# CubSat2.net
KiCad netlist of a schematic drawn in Altium Designer
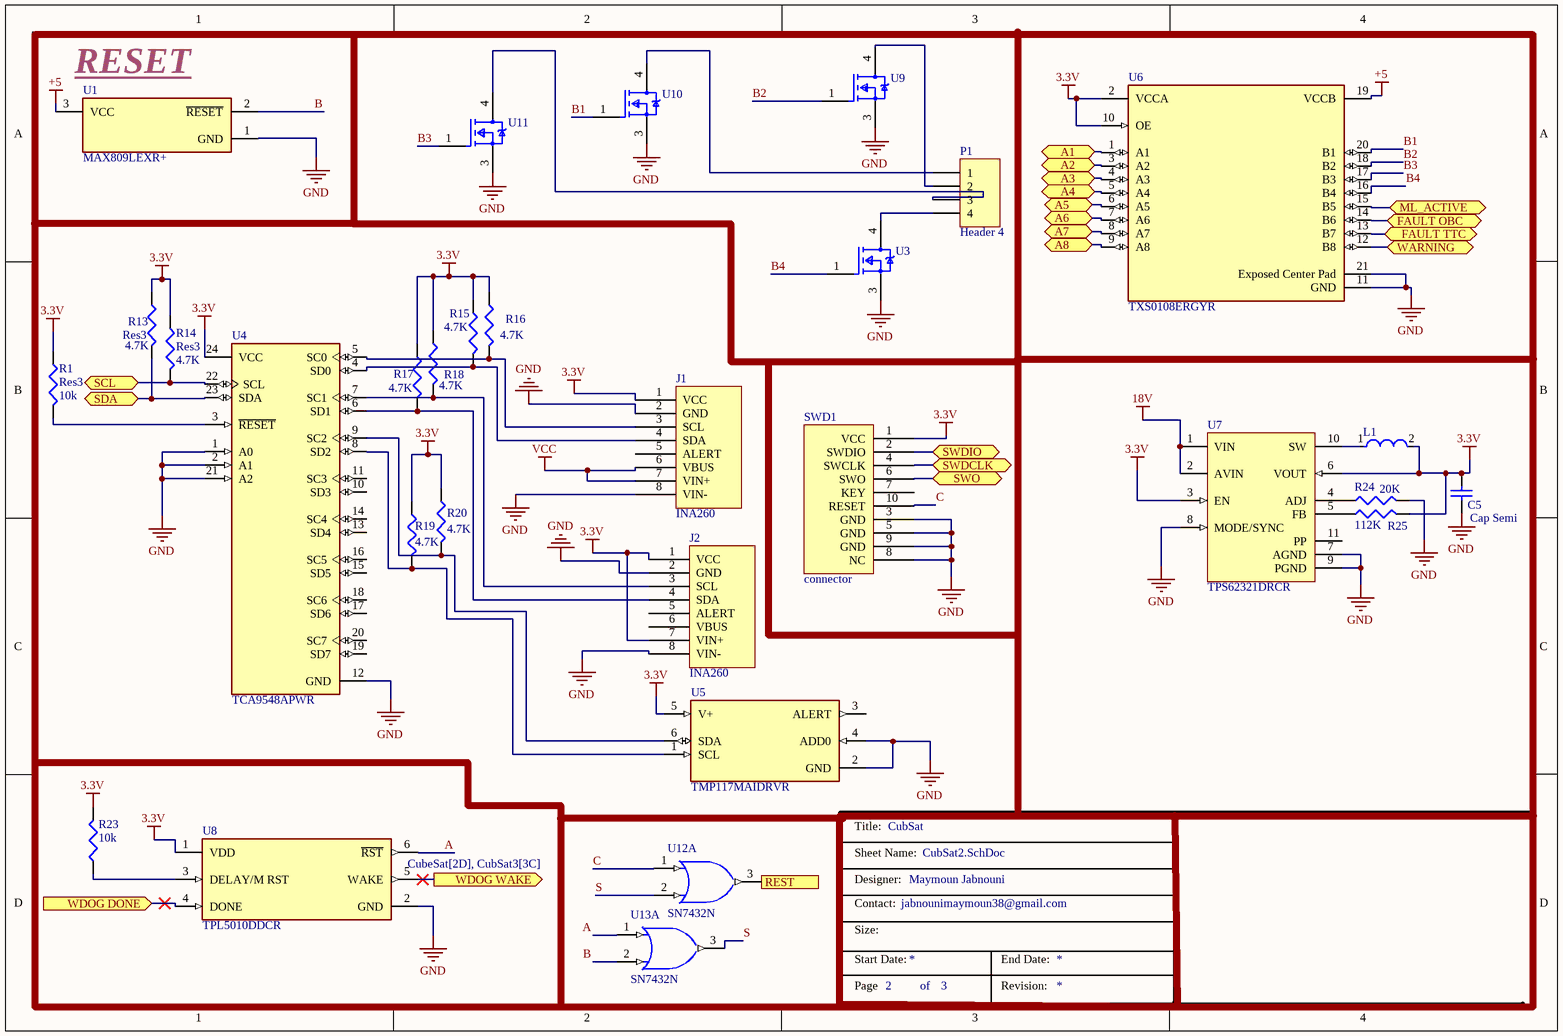
[diagram p0: CubSat2.SchDoc]

(export (version "E")
  (design (tool "Eeschema 10.0.6"))
  (components
    (comp (ref "C5")
      (value "Cap Semi")
      (footprint "C1206")
      (description "Capacitor (Semiconductor SIM Model)")
      (fields (field (name "PUBLISHER") "Altium Limited"))
      (libsource (lib "Miscellaneous Devices") (part "Cap Semi"))
    )
    (comp (ref "J1") (value "INA260") (footprint "INA260") (libsource (lib "CubSat") (part "INA260")))
    (comp (ref "J2") (value "INA260") (footprint "INA260") (libsource (lib "CubSat") (part "INA260")))
    (comp (ref "L1")
      (value "LQW31HN64NJ03L")
      (footprint "FP-LQW31HN_03-MFG")
      (description "Wire Wound RF Inductor 64nH ±5% 0.252Ω 290mA 1206")
      (fields (field (name "TOLERANCE") "5%"))
      (libsource (lib "Altium Content Vault") (part "725321dda6339637d4d059423bc1c3c"))
    )
    (comp (ref "P1")
      (value "Header 4")
      (footprint "HDR1X4")
      (description "Header, 4-Pin")
      (fields (field (name "PUBLISHER") "Altium Limited"))
      (libsource (lib "Miscellaneous Connectors") (part "Header 4"))
    )
    (comp (ref "R1")
      (value "Res3")
      (footprint "J1-0603")
      (description "Resistor")
      (fields (field (name "ALTIUM_VALUE") "10k") (field (name "PUBLISHER") "Altium Limited"))
      (libsource (lib "Miscellaneous Devices") (part "Res3"))
    )
    (comp (ref "R13")
      (value "Res3")
      (footprint "J1-0603")
      (description "Resistor")
      (fields (field (name "ALTIUM_VALUE") "4.7K") (field (name "PUBLISHER") "Altium Limited"))
      (libsource (lib "Miscellaneous Devices") (part "Res3"))
    )
    (comp (ref "R14")
      (value "Res3")
      (footprint "J1-0603")
      (description "Resistor")
      (fields (field (name "ALTIUM_VALUE") "4.7K") (field (name "PUBLISHER") "Altium Limited"))
      (libsource (lib "Miscellaneous Devices") (part "Res3"))
    )
    (comp (ref "R15")
      (value "4.7K")
      (footprint "J1-0603")
      (description "Resistor")
      (fields (field (name "Comment") "Res3") (field (name "PUBLISHER") "Altium Limited"))
      (libsource (lib "Miscellaneous Devices") (part "Res3"))
    )
    (comp (ref "R16")
      (value "4.7K")
      (footprint "J1-0603")
      (description "Resistor")
      (fields (field (name "Comment") "Res3") (field (name "PUBLISHER") "Altium Limited"))
      (libsource (lib "Miscellaneous Devices") (part "Res3"))
    )
    (comp (ref "R17")
      (value "4.7K")
      (footprint "J1-0603")
      (description "Resistor")
      (fields (field (name "Comment") "Res3") (field (name "PUBLISHER") "Altium Limited"))
      (libsource (lib "Miscellaneous Devices") (part "Res3"))
    )
    (comp (ref "R18")
      (value "4.7K")
      (footprint "J1-0603")
      (description "Resistor")
      (fields (field (name "Comment") "Res3") (field (name "PUBLISHER") "Altium Limited"))
      (libsource (lib "Miscellaneous Devices") (part "Res3"))
    )
    (comp (ref "R19")
      (value "4.7K")
      (footprint "J1-0603")
      (description "Resistor")
      (fields (field (name "Comment") "Res3") (field (name "PUBLISHER") "Altium Limited"))
      (libsource (lib "Miscellaneous Devices") (part "Res3"))
    )
    (comp (ref "R20")
      (value "4.7K")
      (footprint "J1-0603")
      (description "Resistor")
      (fields (field (name "Comment") "Res3") (field (name "PUBLISHER") "Altium Limited"))
      (libsource (lib "Miscellaneous Devices") (part "Res3"))
    )
    (comp (ref "R23")
      (value "10k")
      (footprint "J1-0603")
      (description "Resistor")
      (fields (field (name "Comment") "Res3") (field (name "PUBLISHER") "Altium Limited"))
      (libsource (lib "Miscellaneous Devices") (part "Res3"))
    )
    (comp (ref "R24")
      (value "20K")
      (footprint "J1-0603")
      (description "Resistor")
      (fields (field (name "Comment") "Res3") (field (name "PUBLISHER") "Altium Limited"))
      (libsource (lib "Miscellaneous Devices") (part "Res3"))
    )
    (comp (ref "R25")
      (value "112K")
      (footprint "J1-0603")
      (description "Resistor")
      (fields (field (name "Comment") "Res3") (field (name "PUBLISHER") "Altium Limited"))
      (libsource (lib "Miscellaneous Devices") (part "Res3"))
    )
    (comp (ref "SWD1") (value "connector") (footprint "SWD") (libsource (lib "CubSat") (part "SWD")))
    (comp (ref "U1")
      (value "MAX809LEXR+")
      (footprint "FP-X3-2-IPC_B")
      (description "Supervisory Circuits 3-Pin Microprocessor Reset Circuits")
      (libsource (lib "Altium Content Vault") (part "62d4d69c82f5f3f2c191ca2893cb869"))
    )
    (comp (ref "U3")
      (value "IRLR8743TRLPBF")
      (footprint "FP-PG-TO252-3-MFG")
      (description "MOSFET N-CH 30V 160A DPAK")
      (libsource (lib "Altium Content Vault") (part "1b46a229e508186a6fec6a11ed6f67e"))
    )
    (comp (ref "U4")
      (value "TCA9548APWR")
      (footprint "FP-PW0024A-MFG")
      (description "IC I2C SW 8CH W/RESET 24TSSOP")
      (fields
        (field (name "MANUFACTURER") "Texas Instruments")
        (field (name "OCTOPART") "https://octopart.com/tca9548apwr-texas+instruments-22266789")
      )
      (libsource (lib "Altium Content Vault") (part "aab65143522579f0e88a32f493a4230"))
    )
    (comp (ref "U5")
      (value "TMP117MAIDRVR")
      (footprint "FP-DRV0006B-IPC_C")
      (description "TEMPERATURE SENSOR")
      (libsource (lib "Altium Content Vault") (part "6af1b5b9c3f1ef8afed83eb3745dfc1"))
    )
    (comp (ref "U6")
      (value "TXS0108ERGYR")
      (footprint "FP-RGY0020A-MFG")
      (description "IC TRNSLTR BIDIRECTIONAL 20VQFN")
      (libsource (lib "Altium Content Vault") (part "62533083344eba3d76fe41cba668ce2"))
    )
    (comp (ref "U7")
      (value "TPS62321DRCR")
      (footprint "DRC0010J_V")
      (fields (field (name "MANUFACTURER") "Texas Instruments"))
      (libsource (lib "Altium Content Vault") (part "TI-TPS62321DRC10-2400X1650TP"))
    )
    (comp (ref "U8")
      (value "TPL5010DDCR")
      (footprint "FP-DDC0006A-MFG")
      (description "IC OSC PROG TIMER TSOT23-6")
      (fields
        (field (name "OCTOPART") "https://octopart.com/tpl5010ddcr-texas+instruments-52670268")
        (field (name "MANUFACTURER") "Texas Instruments")
      )
      (libsource (lib "Altium Content Vault") (part "4fbb919c68dfb67fb65f533944335df"))
    )
    (comp (ref "U9")
      (value "IRLR8743TRLPBF")
      (footprint "FP-PG-TO252-3-MFG")
      (description "MOSFET N-CH 30V 160A DPAK")
      (libsource (lib "Altium Content Vault") (part "1b46a229e508186a6fec6a11ed6f67e"))
    )
    (comp (ref "U10")
      (value "IRLR8743TRLPBF")
      (footprint "FP-PG-TO252-3-MFG")
      (description "MOSFET N-CH 30V 160A DPAK")
      (libsource (lib "Altium Content Vault") (part "1b46a229e508186a6fec6a11ed6f67e"))
    )
    (comp (ref "U11")
      (value "IRLR8743TRLPBF")
      (footprint "FP-PG-TO252-3-MFG")
      (description "MOSFET N-CH 30V 160A DPAK")
      (libsource (lib "Altium Content Vault") (part "1b46a229e508186a6fec6a11ed6f67e"))
    )
    (comp (ref "U12")
      (value "SN7432N")
      (footprint "N0014A")
      (description "Quad 2-input positive-OR gates, N0014A, TUBE")
      (fields (field (name "MANUFACTURER") "Texas Instruments") (field (name "GENERIC PART NUMBER") "SN7432"))
      (libsource (lib "Altium Content Vault") (part "TI-OR-4-2IN-14"))
    )
    (comp (ref "U13")
      (value "SN7432N")
      (footprint "N0014A")
      (description "Quad 2-input positive-OR gates, N0014A, TUBE")
      (fields (field (name "MANUFACTURER") "Texas Instruments") (field (name "GENERIC PART NUMBER") "SN7432"))
      (libsource (lib "Altium Content Vault") (part "TI-OR-4-2IN-14"))
    )
  )
  (nets
    (net (code "1") (name "+5") (class "Default")
      (node (ref "U1") (pin "3") (pinfunction "VCC_3") (pintype "power_in"))
      (node (ref "U6") (pin "19") (pinfunction "VCCB_19") (pintype "power_in"))
    )
    (net (code "2") (name "/A") (class "Default")
      (node (ref "U13") (pin "1") (pinfunction "1A_1") (pintype "input"))
      (node (ref "U8") (pin "6") (pinfunction "~{RST}_6") (pintype "output"))
    )
    (net (code "3") (name "/A1") (class "Default")
      (node (ref "U6") (pin "1") (pinfunction "A1_1") (pintype "bidirectional"))
    )
    (net (code "4") (name "/A2") (class "Default")
      (node (ref "U6") (pin "3") (pinfunction "A2_3") (pintype "bidirectional"))
    )
    (net (code "5") (name "/A3") (class "Default")
      (node (ref "U6") (pin "4") (pinfunction "A3_4") (pintype "bidirectional"))
    )
    (net (code "6") (name "/A4") (class "Default")
      (node (ref "U6") (pin "5") (pinfunction "A4_5") (pintype "bidirectional"))
    )
    (net (code "7") (name "/A5") (class "Default")
      (node (ref "U6") (pin "6") (pinfunction "A5_6") (pintype "bidirectional"))
    )
    (net (code "8") (name "/A6") (class "Default")
      (node (ref "U6") (pin "7") (pinfunction "A6_7") (pintype "bidirectional"))
    )
    (net (code "9") (name "/A7") (class "Default")
      (node (ref "U6") (pin "8") (pinfunction "A7_8") (pintype "bidirectional"))
    )
    (net (code "10") (name "/A8") (class "Default")
      (node (ref "U6") (pin "9") (pinfunction "A8_9") (pintype "bidirectional"))
    )
    (net (code "11") (name "/B") (class "Default")
      (node (ref "U1") (pin "2") (pinfunction "~{RESET}_2") (pintype "open_collector"))
      (node (ref "U13") (pin "2") (pinfunction "1B_2") (pintype "input"))
    )
    (net (code "12") (name "/B1") (class "Default")
      (node (ref "U10") (pin "1") (pinfunction "G_1") (pintype "passive"))
      (node (ref "U6") (pin "20") (pinfunction "B1_20") (pintype "bidirectional"))
    )
    (net (code "13") (name "/B2") (class "Default")
      (node (ref "U6") (pin "18") (pinfunction "B2_18") (pintype "bidirectional"))
      (node (ref "U9") (pin "1") (pinfunction "G_1") (pintype "passive"))
    )
    (net (code "14") (name "/B3") (class "Default")
      (node (ref "U11") (pin "1") (pinfunction "G_1") (pintype "passive"))
      (node (ref "U6") (pin "17") (pinfunction "B3_17") (pintype "bidirectional"))
    )
    (net (code "15") (name "/B4") (class "Default")
      (node (ref "U3") (pin "1") (pinfunction "G_1") (pintype "passive"))
      (node (ref "U6") (pin "16") (pinfunction "B4_16") (pintype "bidirectional"))
    )
    (net (code "16") (name "/C") (class "Default")
      (node (ref "SWD1") (pin "10") (pinfunction "RESET_10") (pintype "passive"))
      (node (ref "U12") (pin "1") (pinfunction "1A_1") (pintype "input"))
    )
    (net (code "17") (name "/FAULT OBC") (class "Default")
      (node (ref "U6") (pin "14") (pinfunction "B6_14") (pintype "bidirectional"))
    )
    (net (code "18") (name "/FAULT TTC") (class "Default")
      (node (ref "U6") (pin "13") (pinfunction "B7_13") (pintype "bidirectional"))
    )
    (net (code "19") (name "/ML_ACTIVE") (class "Default")
      (node (ref "U6") (pin "15") (pinfunction "B5_15") (pintype "bidirectional"))
    )
    (net (code "20") (name "/REST") (class "Default")
      (node (ref "U12") (pin "3") (pinfunction "1Y_3") (pintype "output"))
    )
    (net (code "21") (name "/S") (class "Default")
      (node (ref "U12") (pin "2") (pinfunction "1B_2") (pintype "input"))
      (node (ref "U13") (pin "3") (pinfunction "1Y_3") (pintype "output"))
    )
    (net (code "22") (name "/SCL") (class "Default")
      (node (ref "R14") (pin "2") (pinfunction "2_2") (pintype "passive"))
      (node (ref "U4") (pin "22") (pinfunction "SCL_22") (pintype "bidirectional"))
    )
    (net (code "23") (name "/SDA") (class "Default")
      (node (ref "R13") (pin "2") (pinfunction "2_2") (pintype "passive"))
      (node (ref "U4") (pin "23") (pinfunction "SDA_23") (pintype "bidirectional"))
    )
    (net (code "24") (name "/SWDCLK") (class "Default")
      (node (ref "SWD1") (pin "4") (pinfunction "SWCLK_4") (pintype "passive"))
    )
    (net (code "25") (name "/SWDIO") (class "Default")
      (node (ref "SWD1") (pin "2") (pinfunction "SWDIO_2") (pintype "passive"))
    )
    (net (code "26") (name "/SWO") (class "Default")
      (node (ref "SWD1") (pin "6") (pinfunction "SWO_6") (pintype "passive"))
    )
    (net (code "27") (name "/WARNING") (class "Default")
      (node (ref "U6") (pin "12") (pinfunction "B8_12") (pintype "bidirectional"))
    )
    (net (code "28") (name "/WDOG DONE") (class "Default")
      (node (ref "U8") (pin "4") (pinfunction "DONE_4") (pintype "input"))
    )
    (net (code "29") (name "/WDOG WAKE") (class "Default")
      (node (ref "U8") (pin "5") (pinfunction "WAKE_5") (pintype "output"))
    )
    (net (code "30") (name "3.3V") (class "Default")
      (node (ref "C5") (pin "2") (pinfunction "2_2") (pintype "passive"))
      (node (ref "J1") (pin "1") (pinfunction "VCC_1") (pintype "passive"))
      (node (ref "J2") (pin "1") (pinfunction "VCC_1") (pintype "passive"))
      (node (ref "J2") (pin "7") (pinfunction "VIN+_7") (pintype "passive"))
      (node (ref "L1") (pin "2") (pinfunction "2_2") (pintype "passive"))
      (node (ref "R1") (pin "1") (pinfunction "1_1") (pintype "passive"))
      (node (ref "R13") (pin "1") (pinfunction "1_1") (pintype "passive"))
      (node (ref "R14") (pin "1") (pinfunction "1_1") (pintype "passive"))
      (node (ref "R15") (pin "1") (pinfunction "1_1") (pintype "passive"))
      (node (ref "R16") (pin "1") (pinfunction "1_1") (pintype "passive"))
      (node (ref "R17") (pin "1") (pinfunction "1_1") (pintype "passive"))
      (node (ref "R18") (pin "1") (pinfunction "1_1") (pintype "passive"))
      (node (ref "R19") (pin "1") (pinfunction "1_1") (pintype "passive"))
      (node (ref "R20") (pin "1") (pinfunction "1_1") (pintype "passive"))
      (node (ref "R23") (pin "2") (pinfunction "2_2") (pintype "passive"))
      (node (ref "R25") (pin "2") (pinfunction "2_2") (pintype "passive"))
      (node (ref "SWD1") (pin "1") (pinfunction "VCC_1") (pintype "passive"))
      (node (ref "U4") (pin "24") (pinfunction "VCC_24") (pintype "power_in"))
      (node (ref "U5") (pin "5") (pinfunction "V+_5") (pintype "input"))
      (node (ref "U6") (pin "10") (pinfunction "OE_10") (pintype "input"))
      (node (ref "U6") (pin "2") (pinfunction "VCCA_2") (pintype "power_in"))
      (node (ref "U7") (pin "3") (pinfunction "EN_3") (pintype "input"))
      (node (ref "U7") (pin "6") (pinfunction "VOUT_6") (pintype "input"))
      (node (ref "U8") (pin "1") (pinfunction "VDD_1") (pintype "power_in"))
    )
    (net (code "31") (name "18V") (class "Default")
      (node (ref "U7") (pin "1") (pinfunction "VIN_1") (pintype "power_in"))
      (node (ref "U7") (pin "2") (pinfunction "AVIN_2") (pintype "power_in"))
    )
    (net (code "32") (name "GND") (class "Default")
      (node (ref "C5") (pin "1") (pinfunction "1_1") (pintype "passive"))
      (node (ref "J1") (pin "2") (pinfunction "GND_2") (pintype "passive"))
      (node (ref "J1") (pin "8") (pinfunction "VIN-_8") (pintype "passive"))
      (node (ref "J2") (pin "2") (pinfunction "GND_2") (pintype "passive"))
      (node (ref "J2") (pin "8") (pinfunction "VIN-_8") (pintype "passive"))
      (node (ref "R24") (pin "2") (pinfunction "2_2") (pintype "passive"))
      (node (ref "SWD1") (pin "3") (pinfunction "GND_3") (pintype "passive"))
      (node (ref "SWD1") (pin "5") (pinfunction "GND_5") (pintype "passive"))
      (node (ref "SWD1") (pin "8") (pinfunction "NC_8") (pintype "passive"))
      (node (ref "SWD1") (pin "9") (pinfunction "GND_9") (pintype "passive"))
      (node (ref "U1") (pin "1") (pinfunction "GND_1") (pintype "power_in"))
      (node (ref "U10") (pin "3") (pinfunction "S_3") (pintype "passive"))
      (node (ref "U11") (pin "3") (pinfunction "S_3") (pintype "passive"))
      (node (ref "U3") (pin "3") (pinfunction "S_3") (pintype "passive"))
      (node (ref "U4") (pin "1") (pinfunction "A0_1") (pintype "input"))
      (node (ref "U4") (pin "12") (pinfunction "GND_12") (pintype "power_in"))
      (node (ref "U4") (pin "2") (pinfunction "A1_2") (pintype "input"))
      (node (ref "U4") (pin "21") (pinfunction "A2_21") (pintype "input"))
      (node (ref "U5") (pin "2") (pinfunction "GND_2") (pintype "power_in"))
      (node (ref "U5") (pin "4") (pinfunction "ADD0_4") (pintype "input"))
      (node (ref "U6") (pin "11") (pinfunction "GND_11") (pintype "power_in"))
      (node (ref "U6") (pin "21") (pinfunction "Exposed_Center_Pad_21") (pintype "power_in"))
      (node (ref "U7") (pin "7") (pinfunction "AGND_7") (pintype "power_in"))
      (node (ref "U7") (pin "8") (pinfunction "MODE/SYNC_8") (pintype "input"))
      (node (ref "U7") (pin "9") (pinfunction "PGND_9") (pintype "power_in"))
      (node (ref "U8") (pin "2") (pinfunction "GND_2") (pintype "power_in"))
      (node (ref "U9") (pin "3") (pinfunction "S_3") (pintype "passive"))
    )
    (net (code "33") (name "Net-(J1-SCL)") (class "Default")
      (node (ref "J1") (pin "3") (pinfunction "SCL_3") (pintype "passive"))
      (node (ref "R16") (pin "2") (pinfunction "2_2") (pintype "passive"))
      (node (ref "U4") (pin "5") (pinfunction "SC0_5") (pintype "bidirectional"))
    )
    (net (code "34") (name "Net-(J1-SDA)") (class "Default")
      (node (ref "J1") (pin "4") (pinfunction "SDA_4") (pintype "passive"))
      (node (ref "R15") (pin "2") (pinfunction "2_2") (pintype "passive"))
      (node (ref "U4") (pin "4") (pinfunction "SD0_4") (pintype "bidirectional"))
    )
    (net (code "35") (name "Net-(J2-SCL)") (class "Default")
      (node (ref "J2") (pin "3") (pinfunction "SCL_3") (pintype "passive"))
      (node (ref "R18") (pin "2") (pinfunction "2_2") (pintype "passive"))
      (node (ref "U4") (pin "7") (pinfunction "SC1_7") (pintype "bidirectional"))
    )
    (net (code "36") (name "Net-(J2-SDA)") (class "Default")
      (node (ref "J2") (pin "4") (pinfunction "SDA_4") (pintype "passive"))
      (node (ref "R17") (pin "2") (pinfunction "2_2") (pintype "passive"))
      (node (ref "U4") (pin "6") (pinfunction "SD1_6") (pintype "bidirectional"))
    )
    (net (code "37") (name "Net-(U3-D)") (class "Default")
      (node (ref "P1") (pin "4") (pinfunction "4_4") (pintype "passive"))
      (node (ref "U3") (pin "4") (pinfunction "D_4") (pintype "passive"))
    )
    (net (code "38") (name "Net-(U4-SC2)") (class "Default")
      (node (ref "R20") (pin "2") (pinfunction "2_2") (pintype "passive"))
      (node (ref "U4") (pin "9") (pinfunction "SC2_9") (pintype "bidirectional"))
      (node (ref "U5") (pin "6") (pinfunction "SDA_6") (pintype "bidirectional"))
    )
    (net (code "39") (name "Net-(U4-SD2)") (class "Default")
      (node (ref "R19") (pin "2") (pinfunction "2_2") (pintype "passive"))
      (node (ref "U4") (pin "8") (pinfunction "SD2_8") (pintype "bidirectional"))
      (node (ref "U5") (pin "1") (pinfunction "SCL_1") (pintype "input"))
    )
    (net (code "40") (name "Net-(U4-~{RESET})") (class "Default")
      (node (ref "R1") (pin "2") (pinfunction "2_2") (pintype "passive"))
      (node (ref "U4") (pin "3") (pinfunction "~{RESET}_3") (pintype "input"))
    )
    (net (code "41") (name "Net-(U7-ADJ)") (class "Default")
      (node (ref "R24") (pin "1") (pinfunction "1_1") (pintype "passive"))
      (node (ref "U7") (pin "4") (pinfunction "ADJ_4") (pintype "passive"))
    )
    (net (code "42") (name "Net-(U7-FB)") (class "Default")
      (node (ref "R25") (pin "1") (pinfunction "1_1") (pintype "passive"))
      (node (ref "U7") (pin "5") (pinfunction "FB_5") (pintype "passive"))
    )
    (net (code "43") (name "Net-(U7-SW)") (class "Default")
      (node (ref "L1") (pin "1") (pinfunction "1_1") (pintype "passive"))
      (node (ref "U7") (pin "10") (pinfunction "SW_10") (pintype "power_in"))
    )
    (net (code "44") (name "Net-(U8-DELAY{slash}M_RST)") (class "Default")
      (node (ref "R23") (pin "1") (pinfunction "1_1") (pintype "passive"))
      (node (ref "U8") (pin "3") (pinfunction "DELAY/M_RST_3") (pintype "input"))
    )
    (net (code "45") (name "Net-(U9-D)") (class "Default")
      (node (ref "P1") (pin "2") (pinfunction "2_2") (pintype "passive"))
      (node (ref "U9") (pin "4") (pinfunction "D_4") (pintype "passive"))
    )
    (net (code "46") (name "Net-(U10-D)") (class "Default")
      (node (ref "P1") (pin "1") (pinfunction "1_1") (pintype "passive"))
      (node (ref "U10") (pin "4") (pinfunction "D_4") (pintype "passive"))
    )
    (net (code "47") (name "Net-(U11-D)") (class "Default")
      (node (ref "P1") (pin "3") (pinfunction "3_3") (pintype "passive"))
      (node (ref "U11") (pin "4") (pinfunction "D_4") (pintype "passive"))
    )
    (net (code "48") (name "VCC") (class "Default")
      (node (ref "J1") (pin "6") (pinfunction "VBUS_6") (pintype "passive"))
      (node (ref "J1") (pin "7") (pinfunction "VIN+_7") (pintype "passive"))
    )
    (net (code "49") (name "unconnected-(J1-ALERT-Pad5)") (class "Default")
      (node (ref "J1") (pin "5") (pinfunction "ALERT_5") (pintype "passive"))
    )
    (net (code "50") (name "unconnected-(J2-ALERT-Pad5)") (class "Default")
      (node (ref "J2") (pin "5") (pinfunction "ALERT_5") (pintype "passive"))
    )
    (net (code "51") (name "unconnected-(J2-VBUS-Pad6)") (class "Default")
      (node (ref "J2") (pin "6") (pinfunction "VBUS_6") (pintype "passive"))
    )
    (net (code "52") (name "unconnected-(SWD1-KEY-Pad7)") (class "Default")
      (node (ref "SWD1") (pin "7") (pinfunction "KEY_7") (pintype "passive"))
    )
    (net (code "53") (name "unconnected-(U4-SC3-Pad11)") (class "Default")
      (node (ref "U4") (pin "11") (pinfunction "SC3_11") (pintype "bidirectional"))
    )
    (net (code "54") (name "unconnected-(U4-SC4-Pad14)") (class "Default")
      (node (ref "U4") (pin "14") (pinfunction "SC4_14") (pintype "bidirectional"))
    )
    (net (code "55") (name "unconnected-(U4-SC5-Pad16)") (class "Default")
      (node (ref "U4") (pin "16") (pinfunction "SC5_16") (pintype "bidirectional"))
    )
    (net (code "56") (name "unconnected-(U4-SC6-Pad18)") (class "Default")
      (node (ref "U4") (pin "18") (pinfunction "SC6_18") (pintype "bidirectional"))
    )
    (net (code "57") (name "unconnected-(U4-SC7-Pad20)") (class "Default")
      (node (ref "U4") (pin "20") (pinfunction "SC7_20") (pintype "bidirectional"))
    )
    (net (code "58") (name "unconnected-(U4-SD3-Pad10)") (class "Default")
      (node (ref "U4") (pin "10") (pinfunction "SD3_10") (pintype "bidirectional"))
    )
    (net (code "59") (name "unconnected-(U4-SD4-Pad13)") (class "Default")
      (node (ref "U4") (pin "13") (pinfunction "SD4_13") (pintype "bidirectional"))
    )
    (net (code "60") (name "unconnected-(U4-SD5-Pad15)") (class "Default")
      (node (ref "U4") (pin "15") (pinfunction "SD5_15") (pintype "bidirectional"))
    )
    (net (code "61") (name "unconnected-(U4-SD6-Pad17)") (class "Default")
      (node (ref "U4") (pin "17") (pinfunction "SD6_17") (pintype "bidirectional"))
    )
    (net (code "62") (name "unconnected-(U4-SD7-Pad19)") (class "Default")
      (node (ref "U4") (pin "19") (pinfunction "SD7_19") (pintype "bidirectional"))
    )
    (net (code "63") (name "unconnected-(U5-ALERT-Pad3)") (class "Default")
      (node (ref "U5") (pin "3") (pinfunction "ALERT_3") (pintype "output"))
    )
    (net (code "64") (name "unconnected-(U7-PP-Pad11)") (class "Default")
      (node (ref "U7") (pin "11") (pinfunction "PP_11") (pintype "power_in"))
    )
  )
)
